# Interface.net
KiCad netlist of a schematic drawn in Altium Designer
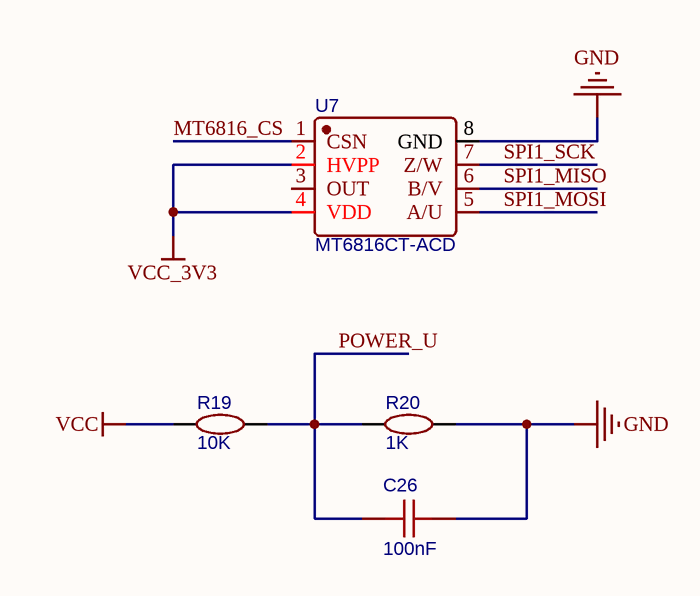
[diagram p0: Interface.SchDoc]

(export (version "E")
  (design (tool "Eeschema 10.0.6"))
  (components
    (comp (ref "C26")
      (value "100nF")
      (footprint "C0603")
      (fields
        (field (name "BOM_MANUFACTURER PART") "CL10B104KB8NNNC")
        (field (name "BOM_SUPPLIER PART") "C1591")
      )
      (libsource (lib "0.1uF") (part "100nF"))
    )
    (comp (ref "R19")
      (value "10K")
      (footprint "R0603")
      (fields
        (field (name "BOM_MANUFACTURER PART") "0603WAF1002T5E")
        (field (name "BOM_SUPPLIER PART") "C25804")
      )
      (libsource (lib "10K") (part "10K"))
    )
    (comp (ref "R20")
      (value "1K")
      (footprint "R0603")
      (fields
        (field (name "BOM_MANUFACTURER PART") "0603WAF1001T5E")
        (field (name "BOM_SUPPLIER PART") "C21190")
      )
      (libsource (lib "1K") (part "1K"))
    )
    (comp (ref "U7")
      (value "MT6816CT-ACD")
      (footprint "SOP-8_L5.0-W4.0-P1.27-LS6.0-BL")
      (fields (field (name "BOM_SUPPLIER PART") "C879560") (field (name "CONTRIBUTOR") "LCSC"))
      (libsource (lib "MT6816") (part "MT6816CT-ACD"))
    )
  )
  (nets
    (net (code "1") (name "/MT6816_CS") (class "Default")
      (node (ref "U7") (pin "1") (pinfunction "CSN_1") (pintype "passive"))
    )
    (net (code "2") (name "/POWER_U") (class "Default")
      (node (ref "C26") (pin "1") (pinfunction "1_1") (pintype "passive"))
      (node (ref "R19") (pin "2") (pinfunction "2_2") (pintype "passive"))
      (node (ref "R20") (pin "1") (pinfunction "1_1") (pintype "passive"))
    )
    (net (code "3") (name "/SPI1_MISO") (class "Default")
      (node (ref "U7") (pin "6") (pinfunction "B/V_6") (pintype "passive"))
    )
    (net (code "4") (name "/SPI1_MOSI") (class "Default")
      (node (ref "U7") (pin "5") (pinfunction "A/U_5") (pintype "passive"))
    )
    (net (code "5") (name "/SPI1_SCK") (class "Default")
      (node (ref "U7") (pin "7") (pinfunction "Z/W_7") (pintype "passive"))
    )
    (net (code "6") (name "GND") (class "Default")
      (node (ref "C26") (pin "2") (pinfunction "2_2") (pintype "passive"))
      (node (ref "R20") (pin "2") (pinfunction "2_2") (pintype "passive"))
      (node (ref "U7") (pin "8") (pinfunction "GND_8") (pintype "passive"))
    )
    (net (code "7") (name "VCC") (class "Default")
      (node (ref "R19") (pin "1") (pinfunction "1_1") (pintype "passive"))
    )
    (net (code "8") (name "VCC_3V3") (class "Default")
      (node (ref "U7") (pin "2") (pinfunction "HVPP_2") (pintype "passive"))
      (node (ref "U7") (pin "4") (pinfunction "VDD_4") (pintype "passive"))
    )
    (net (code "9") (name "unconnected-(U7-OUT-Pad3)") (class "Default")
      (node (ref "U7") (pin "3") (pinfunction "OUT_3") (pintype "passive"))
    )
  )
)
